# Compute_Module_TOP.net
KiCad netlist of a schematic drawn in Altium Designer
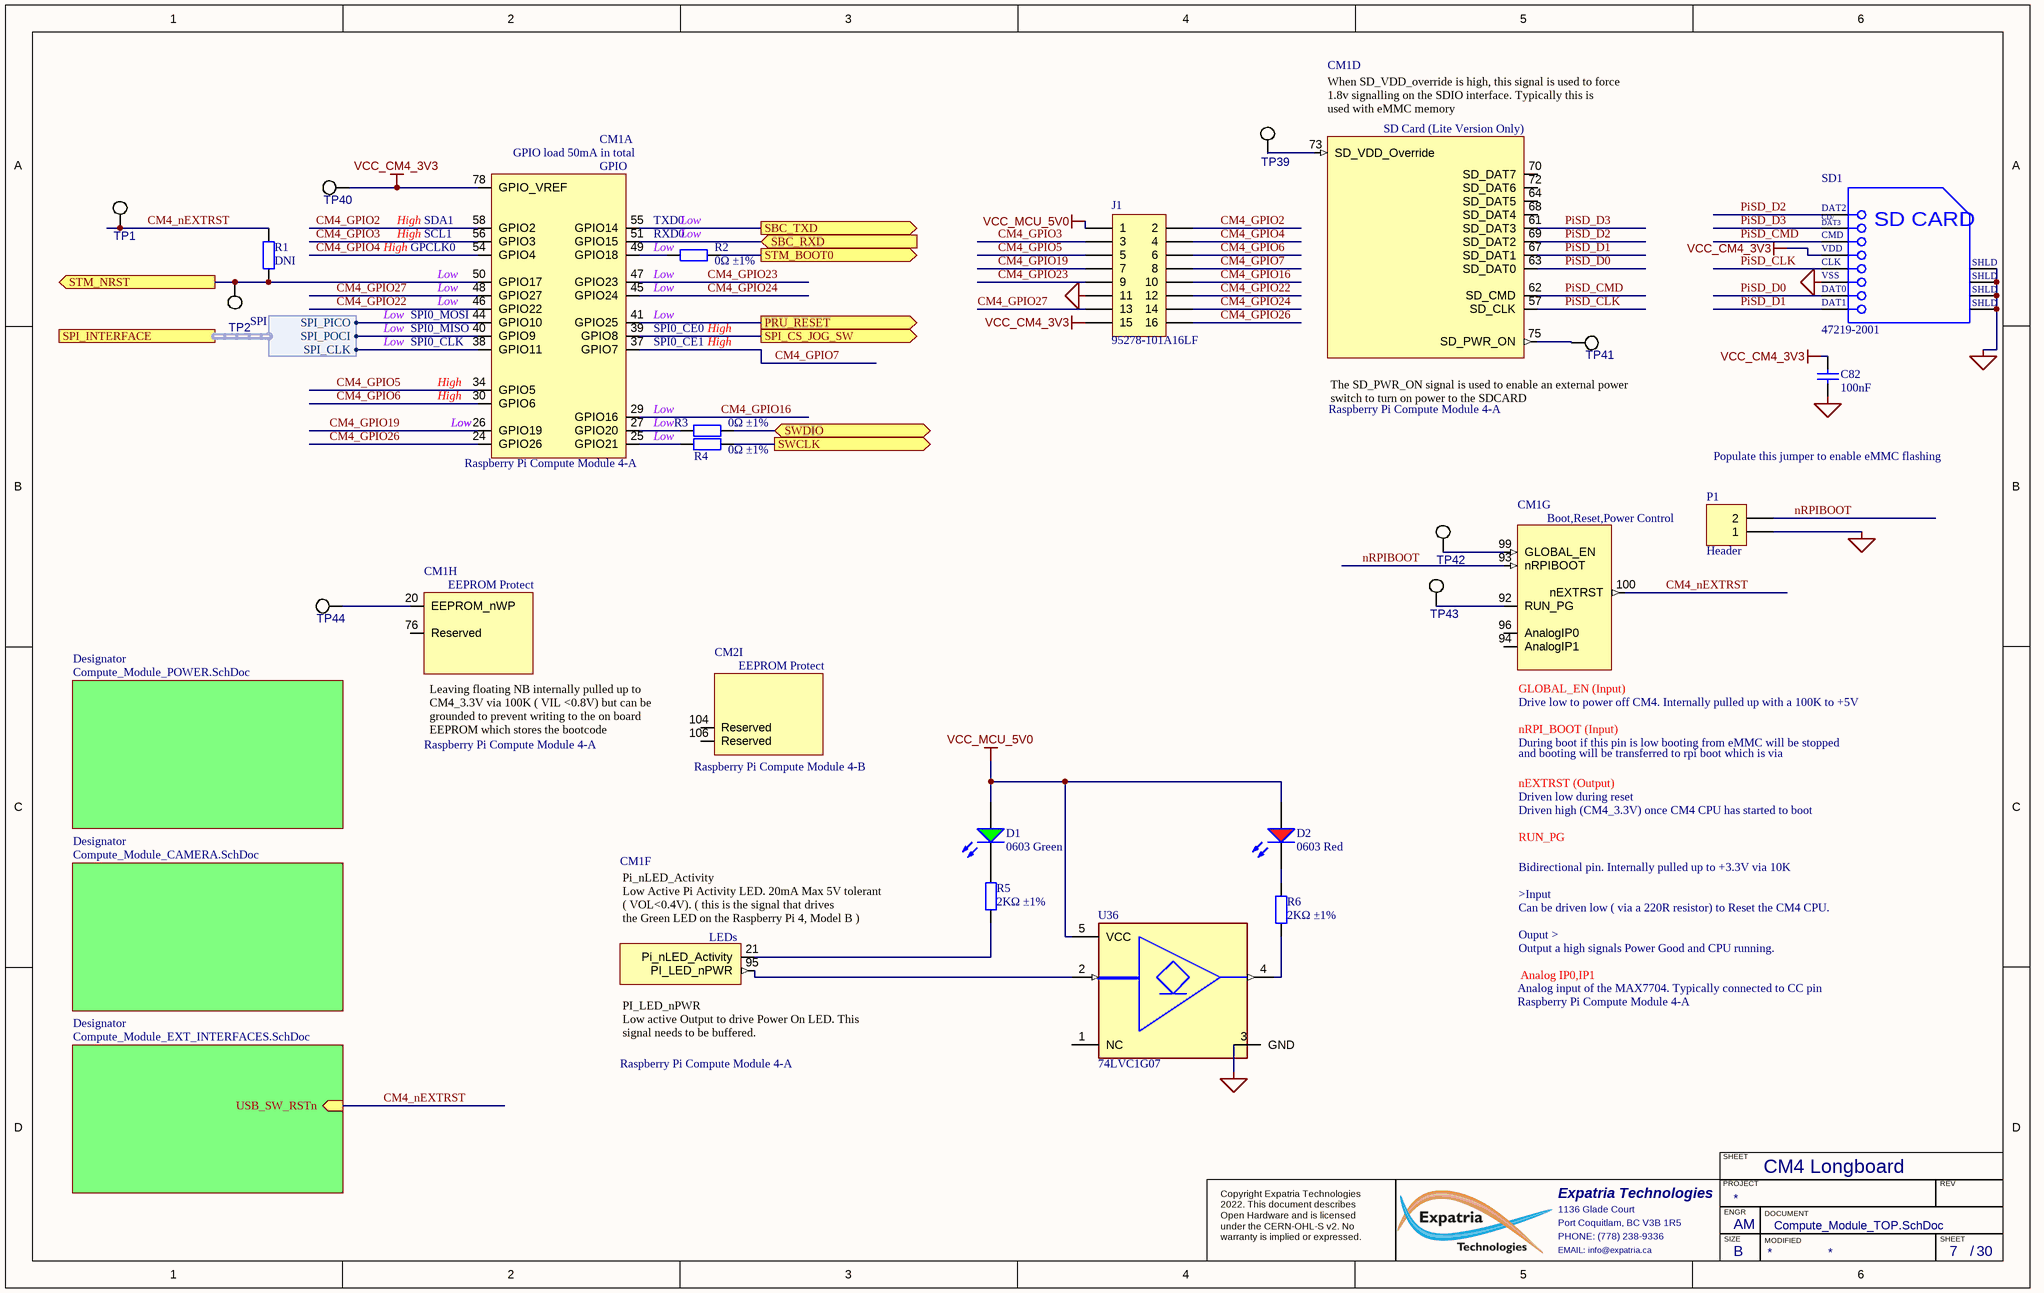
[diagram p0: Compute_Module_TOP.SchDoc]

(export (version "E")
  (design (tool "Eeschema 10.0.6"))
  (components
    (comp (ref "C82")
      (value "100nF")
      (footprint "0603_C")
      (description "Chip capacitors")
      (fields
        (field (name "MANUFACTURER") "YAGEO")
        (field (name "MANUFACTURER PART NUMBER") "CC0603KRX7R9BB104")
      )
      (libsource (lib "Cap") (part "0603 100nF (104) 10% 50V"))
    )
    (comp (ref "CM1")
      (value "Raspberry Pi Compute Module 4-A")
      (footprint "DF40HC30100DS04V51")
      (description "Raspberry Pi Compute Module 4 Pins 1-100 (Connector A)")
      (fields
        (field (name "MANUFACTURER") "Hirose")
        (field (name "MANUFACTURER PART NUMBER") "DF40HC(3.0)-100DS-0.4V(51)")
      )
      (libsource (lib "Sienci_Labs") (part "CM4_Module_A"))
    )
    (comp (ref "CM2")
      (value "Raspberry Pi Compute Module 4-B")
      (footprint "DF40HC30100DS04V51 - p101-200")
      (description "Raspberry Pi Compute Module 4 Pins 101-200 (Connector B)")
      (fields
        (field (name "MANUFACTURER") "Hirose")
        (field (name "MANUFACTURER PART NUMBER") "DF40HC(3.0)-100DS-0.4V(51)")
      )
      (libsource (lib "Sienci_Labs") (part "CM4_Module_B"))
    )
    (comp (ref "D1")
      (value "0603 Green")
      (footprint "0603_LED_S1")
      (description "LED")
      (fields
        (field (name "MANUFACTURER PART NUMBER") "19-217/GHC-YR1S2/3T")
        (field (name "MANUFACTURER") "Everlight Elec")
      )
      (libsource (lib "LED") (part "0603 LED Green"))
    )
    (comp (ref "D2")
      (value "0603 Red")
      (footprint "0603_LED_S1")
      (fields
        (field (name "MANUFACTURER") "Everlight Elec")
        (field (name "MANUFACTURER PART NUMBER") "19-213SURC/S530-A3/TR8")
      )
      (libsource (lib "Sienci_Labs") (part "19-213SURC/S530-A3/TR8"))
    )
    (comp (ref "J1")
      (value "95278-101A16LF")
      (footprint "95278101A16LF")
      (description "Conn Unshrouded Header HDR 16 POS 2.54mm Solder ST Top Entry SMD BergStik® T/R")
      (fields (field (name "MANUFACTURER") "Amphenol ICC / FCI"))
      (libsource (lib "Sienci_Labs") (part "95278-101A16LF"))
    )
    (comp (ref "P1")
      (value "Header")
      (footprint "HDR1X2")
      (description "Straight Square Pins 2 2.54mm Black Brass 1x2P Plugin,P=2.54mm Pin Headers ROHS")
      (fields
        (field (name "MANUFACTURER") "MOLEX")
        (field (name "MANUFACTURER PART NUMBER") "22284020")
        (field (name "PUBLISHER") "Altium Limited")
      )
      (libsource (lib "Sienci_Labs") (part "Header 2"))
    )
    (comp (ref "R1")
      (value "DNI")
      (footprint "0603_R")
      (description "Chip resistor")
      (fields (field (name "MANUFACTURER") "Uniroyal Elec") (field (name "PARTNUMBER") "0603WAF2001T5E"))
      (libsource (lib "RES") (part "0603 2K (2001) 1%"))
    )
    (comp (ref "R2")
      (value "0Ω ±1%")
      (footprint "0603_R")
      (description "Chip resistor")
      (fields (field (name "MANUFACTURER") "Uniroyal Elec") (field (name "PARTNUMBER") "0603WAF0000T5E"))
      (libsource (lib "RES") (part "0603 0R (0R0) 1%"))
    )
    (comp (ref "R3")
      (value "0Ω ±1%")
      (footprint "0603_R")
      (description "Chip resistor")
      (fields (field (name "MANUFACTURER") "Uniroyal Elec") (field (name "PARTNUMBER") "0603WAF0000T5E"))
      (libsource (lib "RES") (part "0603 0R (0R0) 1%"))
    )
    (comp (ref "R4")
      (value "0Ω ±1%")
      (footprint "0603_R")
      (description "Chip resistor")
      (fields (field (name "MANUFACTURER") "Uniroyal Elec") (field (name "PARTNUMBER") "0603WAF0000T5E"))
      (libsource (lib "RES") (part "0603 0R (0R0) 1%"))
    )
    (comp (ref "R5")
      (value "2KΩ ±1%")
      (footprint "0603_R")
      (description "Chip resistor")
      (fields (field (name "MANUFACTURER") "Uniroyal Elec") (field (name "PARTNUMBER") "0603WAF2001T5E"))
      (libsource (lib "RES") (part "0603 2K (2001) 1%"))
    )
    (comp (ref "R6")
      (value "2KΩ ±1%")
      (footprint "0603_R")
      (description "Chip resistor")
      (fields (field (name "MANUFACTURER") "Uniroyal Elec") (field (name "PARTNUMBER") "0603WAF2001T5E"))
      (libsource (lib "RES") (part "0603 2K (2001) 1%"))
    )
    (comp (ref "SD1")
      (value "47219-2001")
      (footprint "472192001")
      (description "Conn Micro SD Card SKT 8 POS 1.1mm Solder RA SMD 0.5A/Contact Embossed T/R")
      (fields (field (name "MANUFACTURER") "Molex"))
      (libsource (lib "Sienci_Labs") (part "47219-2001"))
    )
    (comp (ref "TP1")
      (value "TESTPOINT")
      (footprint "TP/SMALL")
      (description "Test Point")
      (libsource (lib "Sienci_Labs") (part "TESTPOINT"))
    )
    (comp (ref "TP2")
      (value "TESTPOINT")
      (footprint "TP/SMALL")
      (description "Test Point")
      (libsource (lib "") (part "TESTPOINT_1"))
    )
    (comp (ref "TP39")
      (value "TESTPOINT")
      (footprint "TP/SMALL")
      (description "Test Point")
      (libsource (lib "Sienci_Labs") (part "TESTPOINT"))
    )
    (comp (ref "TP40")
      (value "TESTPOINT")
      (footprint "TP/SMALL")
      (description "Test Point")
      (libsource (lib "") (part "TESTPOINT_2"))
    )
    (comp (ref "TP41")
      (value "TESTPOINT")
      (footprint "TP/SMALL")
      (description "Test Point")
      (libsource (lib "") (part "TESTPOINT_3"))
    )
    (comp (ref "TP42")
      (value "TESTPOINT")
      (footprint "TP/SMALL")
      (description "Test Point")
      (libsource (lib "Sienci_Labs") (part "TESTPOINT"))
    )
    (comp (ref "TP43")
      (value "TESTPOINT")
      (footprint "TP/SMALL")
      (description "Test Point")
      (libsource (lib "Sienci_Labs") (part "TESTPOINT"))
    )
    (comp (ref "TP44")
      (value "TESTPOINT")
      (footprint "TP/SMALL")
      (description "Test Point")
      (libsource (lib "") (part "TESTPOINT_2"))
    )
    (comp (ref "U36")
      (value "74LVC1G07")
      (footprint "SOT65P210X110-5N")
      (description "IC BUF NON-INVERT 5.5V SOT353")
      (fields (field (name "MANUFACTURER") "Wuxi I-core Elec"))
      (libsource (lib "Sienci_Labs") (part "74LVC1G07"))
    )
  )
  (nets
    (net (code "2") (name "/CM4_GPIO2") (class "Default")
      (node (ref "CM1") (pin "58") (pinfunction "GPIO2_58") (pintype "passive"))
      (node (ref "J1") (pin "2") (pinfunction "2_2") (pintype "passive"))
    )
    (net (code "3") (name "/CM4_GPIO3") (class "Default")
      (node (ref "CM1") (pin "56") (pinfunction "GPIO3_56") (pintype "passive"))
      (node (ref "J1") (pin "3") (pinfunction "3_3") (pintype "passive"))
    )
    (net (code "4") (name "/CM4_GPIO4") (class "Default")
      (node (ref "CM1") (pin "54") (pinfunction "GPIO4_54") (pintype "passive"))
      (node (ref "J1") (pin "4") (pinfunction "4_4") (pintype "passive"))
    )
    (net (code "5") (name "/CM4_GPIO5") (class "Default")
      (node (ref "CM1") (pin "34") (pinfunction "GPIO5_34") (pintype "passive"))
      (node (ref "J1") (pin "5") (pinfunction "5_5") (pintype "passive"))
    )
    (net (code "6") (name "/CM4_GPIO6") (class "Default")
      (node (ref "CM1") (pin "30") (pinfunction "GPIO6_30") (pintype "passive"))
      (node (ref "J1") (pin "6") (pinfunction "6_6") (pintype "passive"))
    )
    (net (code "7") (name "/CM4_GPIO7") (class "Default")
      (node (ref "CM1") (pin "37") (pinfunction "GPIO7_37") (pintype "passive"))
      (node (ref "J1") (pin "8") (pinfunction "8_8") (pintype "passive"))
    )
    (net (code "8") (name "/CM4_GPIO16") (class "Default")
      (node (ref "CM1") (pin "29") (pinfunction "GPIO16_29") (pintype "passive"))
      (node (ref "J1") (pin "10") (pinfunction "10_10") (pintype "passive"))
    )
    (net (code "9") (name "/CM4_GPIO19") (class "Default")
      (node (ref "CM1") (pin "26") (pinfunction "GPIO19_26") (pintype "passive"))
      (node (ref "J1") (pin "7") (pinfunction "7_7") (pintype "passive"))
    )
    (net (code "10") (name "/CM4_GPIO22") (class "Default")
      (node (ref "CM1") (pin "46") (pinfunction "GPIO22_46") (pintype "passive"))
      (node (ref "J1") (pin "12") (pinfunction "12_12") (pintype "passive"))
    )
    (net (code "11") (name "/CM4_GPIO23") (class "Default")
      (node (ref "CM1") (pin "47") (pinfunction "GPIO23_47") (pintype "passive"))
      (node (ref "J1") (pin "9") (pinfunction "9_9") (pintype "passive"))
    )
    (net (code "12") (name "/CM4_GPIO24") (class "Default")
      (node (ref "CM1") (pin "45") (pinfunction "GPIO24_45") (pintype "passive"))
      (node (ref "J1") (pin "14") (pinfunction "14_14") (pintype "passive"))
    )
    (net (code "13") (name "/CM4_GPIO26") (class "Default")
      (node (ref "CM1") (pin "24") (pinfunction "GPIO26_24") (pintype "passive"))
      (node (ref "J1") (pin "16") (pinfunction "16_16") (pintype "passive"))
    )
    (net (code "14") (name "/CM4_GPIO27") (class "Default")
      (node (ref "CM1") (pin "48") (pinfunction "GPIO27_48") (pintype "passive"))
      (node (ref "J1") (pin "13") (pinfunction "13_13") (pintype "passive"))
    )
    (net (code "15") (name "/CM4_nEXTRST") (class "Default")
      (node (ref "CM1") (pin "100") (pinfunction "nEXTRST_100") (pintype "output"))
      (node (ref "R1") (pin "2") (pinfunction "2_2") (pintype "passive"))
      (node (ref "TP1") (pin "1") (pintype "passive"))
    )
    (net (code "16") (name "/PRU_RESET") (class "Default")
      (node (ref "CM1") (pin "41") (pinfunction "GPIO25_41") (pintype "passive"))
    )
    (net (code "17") (name "/PiSD_CLK") (class "Default")
      (node (ref "CM1") (pin "57") (pinfunction "SD_CLK_57") (pintype "passive"))
      (node (ref "SD1") (pin "5") (pinfunction "CLK_5") (pintype "passive"))
    )
    (net (code "18") (name "/PiSD_CMD") (class "Default")
      (node (ref "CM1") (pin "62") (pinfunction "SD_CMD_62") (pintype "passive"))
      (node (ref "SD1") (pin "3") (pinfunction "CMD_3") (pintype "passive"))
    )
    (net (code "19") (name "/PiSD_D0") (class "Default")
      (node (ref "CM1") (pin "63") (pinfunction "SD_DAT0_63") (pintype "passive"))
      (node (ref "SD1") (pin "7") (pinfunction "DAT0_7") (pintype "passive"))
    )
    (net (code "20") (name "/PiSD_D1") (class "Default")
      (node (ref "CM1") (pin "67") (pinfunction "SD_DAT1_67") (pintype "passive"))
      (node (ref "SD1") (pin "8") (pinfunction "DAT1_8") (pintype "passive"))
    )
    (net (code "21") (name "/PiSD_D2") (class "Default")
      (node (ref "CM1") (pin "69") (pinfunction "SD_DAT2_69") (pintype "passive"))
      (node (ref "SD1") (pin "1") (pinfunction "DAT2_1") (pintype "passive"))
    )
    (net (code "22") (name "/PiSD_D3") (class "Default")
      (node (ref "CM1") (pin "61") (pinfunction "SD_DAT3_61") (pintype "passive"))
      (node (ref "SD1") (pin "2") (pinfunction "CD/DAT3_2") (pintype "passive"))
    )
    (net (code "23") (name "/SBC_RXD") (class "Default")
      (node (ref "CM1") (pin "51") (pinfunction "GPIO15_51") (pintype "passive"))
    )
    (net (code "24") (name "/SBC_TXD") (class "Default")
      (node (ref "CM1") (pin "55") (pinfunction "GPIO14_55") (pintype "passive"))
    )
    (net (code "25") (name "/SPI_CLK") (class "Default")
      (node (ref "CM1") (pin "38") (pinfunction "GPIO11_38") (pintype "passive"))
    )
    (net (code "26") (name "/SPI_CS_JOG_SW") (class "Default")
      (node (ref "CM1") (pin "39") (pinfunction "GPIO8_39") (pintype "passive"))
    )
    (net (code "27") (name "/SPI_PICO") (class "Default")
      (node (ref "CM1") (pin "44") (pinfunction "GPIO10_44") (pintype "passive"))
    )
    (net (code "28") (name "/SPI_POCI") (class "Default")
      (node (ref "CM1") (pin "40") (pinfunction "GPIO9_40") (pintype "passive"))
    )
    (net (code "29") (name "/STM_BOOT0") (class "Default")
      (node (ref "R2") (pin "1") (pinfunction "1_1") (pintype "passive"))
    )
    (net (code "30") (name "/STM_NRST") (class "Default")
      (node (ref "CM1") (pin "50") (pinfunction "GPIO17_50") (pintype "passive"))
      (node (ref "R1") (pin "1") (pinfunction "1_1") (pintype "passive"))
      (node (ref "TP2") (pin "1") (pintype "passive"))
    )
    (net (code "31") (name "/SWCLK") (class "Default")
      (node (ref "R4") (pin "1") (pinfunction "1_1") (pintype "passive"))
    )
    (net (code "32") (name "/SWDIO") (class "Default")
      (node (ref "R3") (pin "1") (pinfunction "1_1") (pintype "passive"))
    )
    (net (code "33") (name "/nRPIBOOT") (class "Default")
      (node (ref "CM1") (pin "93") (pinfunction "nRPIBOOT_93") (pintype "input"))
      (node (ref "P1") (pin "2") (pinfunction "2_2") (pintype "passive"))
    )
    (net (code "35") (name "MCU_GND") (class "Default")
      (node (ref "C82") (pin "1") (pinfunction "1_1") (pintype "passive"))
      (node (ref "J1") (pin "11") (pinfunction "11_11") (pintype "passive"))
      (node (ref "P1") (pin "1") (pinfunction "1_1") (pintype "passive"))
      (node (ref "SD1") (pin "10") (pinfunction "SHLD_10") (pintype "passive"))
      (node (ref "SD1") (pin "11") (pinfunction "SHLD_11") (pintype "passive"))
      (node (ref "SD1") (pin "12") (pinfunction "SHLD_12") (pintype "passive"))
      (node (ref "SD1") (pin "6") (pinfunction "VSS_6") (pintype "passive"))
      (node (ref "SD1") (pin "9") (pinfunction "SHLD_9") (pintype "passive"))
      (node (ref "U36") (pin "3") (pinfunction "GND_3") (pintype "power_in"))
    )
    (net (code "36") (name "Net-(CM1A-GPIO18)") (class "Default")
      (node (ref "CM1") (pin "49") (pinfunction "GPIO18_49") (pintype "passive"))
      (node (ref "R2") (pin "2") (pinfunction "2_2") (pintype "passive"))
    )
    (net (code "37") (name "Net-(CM1A-GPIO20)") (class "Default")
      (node (ref "CM1") (pin "27") (pinfunction "GPIO20_27") (pintype "passive"))
      (node (ref "R3") (pin "2") (pinfunction "2_2") (pintype "passive"))
    )
    (net (code "38") (name "Net-(CM1A-GPIO21)") (class "Default")
      (node (ref "CM1") (pin "25") (pinfunction "GPIO21_25") (pintype "passive"))
      (node (ref "R4") (pin "2") (pinfunction "2_2") (pintype "passive"))
    )
    (net (code "39") (name "Net-(CM1D-SD_PWR_ON)") (class "Default")
      (node (ref "CM1") (pin "75") (pinfunction "SD_PWR_ON_75") (pintype "output"))
      (node (ref "TP41") (pin "1") (pintype "passive"))
    )
    (net (code "40") (name "Net-(CM1D-SD_VDD_Override)") (class "Default")
      (node (ref "CM1") (pin "73") (pinfunction "SD_VDD_Override_73") (pintype "input"))
      (node (ref "TP39") (pin "1") (pintype "passive"))
    )
    (net (code "41") (name "Net-(CM1F-PI_LED_nPWR)") (class "Default")
      (node (ref "CM1") (pin "95") (pinfunction "PI_LED_nPWR_95") (pintype "output"))
      (node (ref "U36") (pin "2") (pinfunction "A_2") (pintype "input"))
    )
    (net (code "42") (name "Net-(CM1F-Pi_nLED_Activity)") (class "Default")
      (node (ref "CM1") (pin "21") (pinfunction "Pi_nLED_Activity_21") (pintype "open_collector"))
      (node (ref "R5") (pin "1") (pinfunction "1_1") (pintype "passive"))
    )
    (net (code "43") (name "Net-(CM1G-GLOBAL_EN)") (class "Default")
      (node (ref "CM1") (pin "99") (pinfunction "GLOBAL_EN_99") (pintype "input"))
      (node (ref "TP42") (pin "1") (pintype "passive"))
    )
    (net (code "44") (name "Net-(CM1G-RUN_PG)") (class "Default")
      (node (ref "CM1") (pin "92") (pinfunction "RUN_PG_92") (pintype "passive"))
      (node (ref "TP43") (pin "1") (pintype "passive"))
    )
    (net (code "45") (name "Net-(CM1H-EEPROM_nWP)") (class "Default")
      (node (ref "CM1") (pin "20") (pinfunction "EEPROM_nWP_20") (pintype "passive"))
      (node (ref "TP44") (pin "1") (pintype "passive"))
    )
    (net (code "46") (name "Net-(D1-PadK)") (class "Default")
      (node (ref "D1") (pin "K") (pinfunction "K_K") (pintype "passive"))
      (node (ref "R5") (pin "2") (pinfunction "2_2") (pintype "passive"))
    )
    (net (code "47") (name "Net-(D2-PadK)") (class "Default")
      (node (ref "D2") (pin "K") (pinfunction "K_K") (pintype "passive"))
      (node (ref "R6") (pin "2") (pinfunction "2_2") (pintype "passive"))
    )
    (net (code "48") (name "Net-(U36-Y)") (class "Default")
      (node (ref "R6") (pin "1") (pinfunction "1_1") (pintype "passive"))
      (node (ref "U36") (pin "4") (pinfunction "Y_4") (pintype "output"))
    )
    (net (code "49") (name "VCC_CM4_3V3") (class "Default")
      (node (ref "C82") (pin "2") (pinfunction "2_2") (pintype "passive"))
      (node (ref "CM1") (pin "78") (pinfunction "GPIO_VREF_78") (pintype "power_in"))
      (node (ref "J1") (pin "15") (pinfunction "15_15") (pintype "passive"))
      (node (ref "SD1") (pin "4") (pinfunction "VDD_4") (pintype "passive"))
      (node (ref "TP40") (pin "1") (pintype "passive"))
    )
    (net (code "50") (name "VCC_MCU_5V0") (class "Default")
      (node (ref "D1") (pin "A") (pinfunction "A_A") (pintype "passive"))
      (node (ref "D2") (pin "A") (pinfunction "A_A") (pintype "passive"))
      (node (ref "J1") (pin "1") (pinfunction "1_1") (pintype "passive"))
      (node (ref "U36") (pin "5") (pinfunction "VCC_5") (pintype "power_in"))
    )
    (net (code "51") (name "unconnected-(CM1D-SD_DAT4-Pad68)") (class "Default")
      (node (ref "CM1") (pin "68") (pinfunction "SD_DAT4_68") (pintype "passive"))
    )
    (net (code "52") (name "unconnected-(CM1D-SD_DAT5-Pad64)") (class "Default")
      (node (ref "CM1") (pin "64") (pinfunction "SD_DAT5_64") (pintype "passive"))
    )
    (net (code "53") (name "unconnected-(CM1D-SD_DAT6-Pad72)") (class "Default")
      (node (ref "CM1") (pin "72") (pinfunction "SD_DAT6_72") (pintype "passive"))
    )
    (net (code "54") (name "unconnected-(CM1D-SD_DAT7-Pad70)") (class "Default")
      (node (ref "CM1") (pin "70") (pinfunction "SD_DAT7_70") (pintype "passive"))
    )
    (net (code "55") (name "unconnected-(CM1G-AnalogIP0-Pad96)") (class "Default")
      (node (ref "CM1") (pin "96") (pinfunction "AnalogIP0_96") (pintype "passive"))
    )
    (net (code "56") (name "unconnected-(CM1G-AnalogIP1-Pad94)") (class "Default")
      (node (ref "CM1") (pin "94") (pinfunction "AnalogIP1_94") (pintype "passive"))
    )
    (net (code "57") (name "unconnected-(CM1H-Reserved-Pad76)") (class "Default")
      (node (ref "CM1") (pin "76") (pinfunction "Reserved_76") (pintype "passive"))
    )
    (net (code "58") (name "unconnected-(CM2I-Reserved-Pad104)") (class "Default")
      (node (ref "CM2") (pin "104") (pinfunction "Reserved_104") (pintype "passive"))
    )
    (net (code "59") (name "unconnected-(CM2I-Reserved-Pad106)") (class "Default")
      (node (ref "CM2") (pin "106") (pinfunction "Reserved_106") (pintype "passive"))
    )
    (net (code "60") (name "unconnected-(U36-NC-Pad1)") (class "Default")
      (node (ref "U36") (pin "1") (pinfunction "NC_1") (pintype "passive"))
    )
  )
)
